# GTwoShield.net
KiCad netlist of a schematic drawn in EAGLE
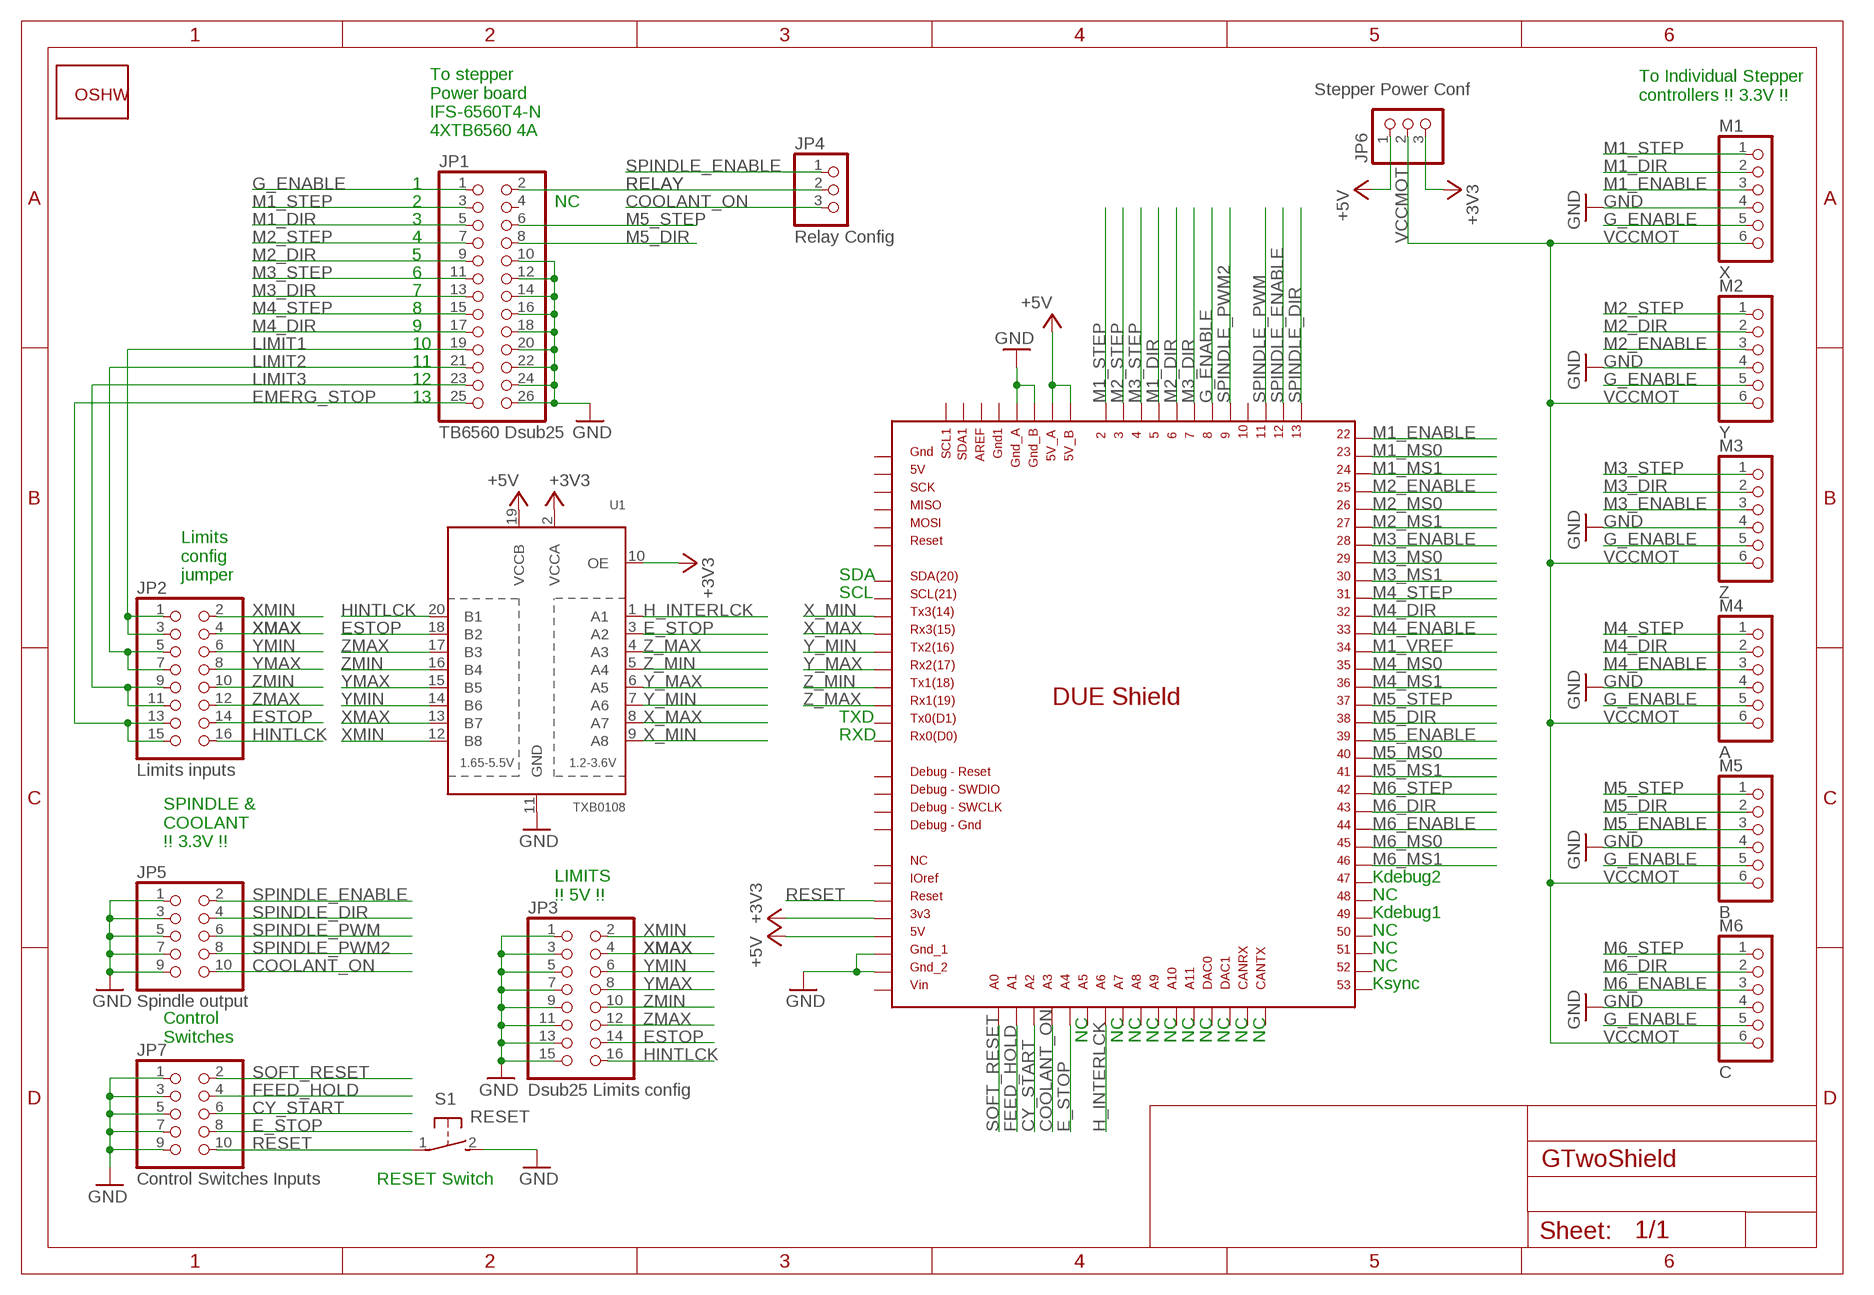
[diagram p0: schematic, sheet 1]

(export (version "E")
  (design (tool "Eeschema 10.0.6"))
  (components
    (comp (ref "GOLD_ORB_SM1")
      (value "OSHWLOGO_GOLD_ORB_MED")
      (footprint "eagle-import:OSHW1")
      (libsource (lib "eagle-import") (part "OSHWLOGO_GOLD_ORB_MED"))
    )
    (comp (ref "JP1")
      (value "TB6560 Dsub25")
      (footprint "eagle-import:2X13")
      (libsource (lib "eagle-import") (part "PINHD-2X13"))
    )
    (comp (ref "JP2")
      (value "Limits inputs")
      (footprint "eagle-import:2X08")
      (libsource (lib "eagle-import") (part "PINHD-2X8"))
    )
    (comp (ref "JP3")
      (value "Dsub25 Limits config")
      (footprint "eagle-import:2X08")
      (libsource (lib "eagle-import") (part "PINHD-2X8"))
    )
    (comp (ref "JP4")
      (value "Relay Config")
      (footprint "eagle-import:1X03")
      (libsource (lib "eagle-import") (part "PINHD-1X3"))
    )
    (comp (ref "JP5")
      (value "Spindle output")
      (footprint "eagle-import:2X05")
      (libsource (lib "eagle-import") (part "PINHD-2X5"))
    )
    (comp (ref "JP6")
      (value "Stepper Power Conf")
      (footprint "eagle-import:1X03")
      (libsource (lib "eagle-import") (part "PINHD-1X3"))
    )
    (comp (ref "JP7")
      (value "Control Switches Inputs")
      (footprint "eagle-import:2X05")
      (libsource (lib "eagle-import") (part "PINHD-2X5"))
    )
    (comp (ref "M1")
      (value "X")
      (footprint "eagle-import:1X06")
      (libsource (lib "eagle-import") (part "PINHD-1X6"))
    )
    (comp (ref "M2")
      (value "Y")
      (footprint "eagle-import:1X06")
      (libsource (lib "eagle-import") (part "PINHD-1X6"))
    )
    (comp (ref "M3")
      (value "Z")
      (footprint "eagle-import:1X06")
      (libsource (lib "eagle-import") (part "PINHD-1X6"))
    )
    (comp (ref "M4")
      (value "A")
      (footprint "eagle-import:1X06")
      (libsource (lib "eagle-import") (part "PINHD-1X6"))
    )
    (comp (ref "M5")
      (value "B")
      (footprint "eagle-import:1X06")
      (libsource (lib "eagle-import") (part "PINHD-1X6"))
    )
    (comp (ref "M6")
      (value "C")
      (footprint "eagle-import:1X06")
      (libsource (lib "eagle-import") (part "PINHD-1X6"))
    )
    (comp (ref "S1")
      (value "RESET")
      (footprint "eagle-import:B3F-31XX")
      (libsource (lib "eagle-import") (part "31-XX"))
    )
    (comp (ref "U$1")
      (value "DUE(NORMAL)")
      (footprint "eagle-import:DUE(NORMAL)")
      (libsource (lib "eagle-import") (part "DUE(NORMAL)"))
    )
    (comp (ref "U1")
      (value "TXB0108")
      (footprint "eagle-import:TSSOP20")
      (libsource (lib "eagle-import") (part "TXB0108PWR"))
    )
  )
  (nets
    (net (code "1") (name "+3V3") (class "Default")
      (node (ref "JP6") (pin "3") (pinfunction "3_3") (pintype "passive"))
      (node (ref "U$1") (pin "3V3") (pinfunction "3V3_3V3") (pintype "bidirectional"))
      (node (ref "U1") (pin "10") (pinfunction "OE_10") (pintype "bidirectional"))
      (node (ref "U1") (pin "2") (pinfunction "VCCA_2") (pintype "bidirectional"))
    )
    (net (code "2") (name "+5V") (class "Default")
      (node (ref "JP6") (pin "1") (pinfunction "1_1") (pintype "passive"))
      (node (ref "U$1") (pin "5V") (pinfunction "5V_5V") (pintype "bidirectional"))
      (node (ref "U$1") (pin "5V_A") (pinfunction "5V_A_5V_A") (pintype "bidirectional"))
      (node (ref "U$1") (pin "5V_B") (pinfunction "5V_B_5V_B") (pintype "bidirectional"))
      (node (ref "U1") (pin "19") (pinfunction "VCCB_19") (pintype "bidirectional"))
    )
    (net (code "3") (name "/COOLANT_ON") (class "Default")
      (node (ref "JP4") (pin "3") (pinfunction "3_3") (pintype "passive"))
      (node (ref "JP5") (pin "10") (pinfunction "10_10") (pintype "passive"))
      (node (ref "U$1") (pin "A3") (pinfunction "A3_A3") (pintype "bidirectional"))
    )
    (net (code "4") (name "/CY_START") (class "Default")
      (node (ref "JP7") (pin "6") (pinfunction "6_6") (pintype "passive"))
      (node (ref "U$1") (pin "A2") (pinfunction "A2_A2") (pintype "bidirectional"))
    )
    (net (code "5") (name "/EMERG_STOP") (class "Default")
      (node (ref "JP1") (pin "25") (pinfunction "25_25") (pintype "passive"))
      (node (ref "JP2") (pin "13") (pinfunction "13_13") (pintype "passive"))
      (node (ref "JP2") (pin "15") (pinfunction "15_15") (pintype "passive"))
    )
    (net (code "6") (name "/ESTOP") (class "Default")
      (node (ref "JP2") (pin "14") (pinfunction "14_14") (pintype "passive"))
      (node (ref "JP3") (pin "14") (pinfunction "14_14") (pintype "passive"))
      (node (ref "U1") (pin "18") (pinfunction "B2_18") (pintype "bidirectional"))
    )
    (net (code "7") (name "/E_STOP") (class "Default")
      (node (ref "JP7") (pin "8") (pinfunction "8_8") (pintype "passive"))
      (node (ref "U$1") (pin "A4") (pinfunction "A4_A4") (pintype "bidirectional"))
      (node (ref "U1") (pin "3") (pinfunction "A2_3") (pintype "bidirectional"))
    )
    (net (code "8") (name "/FEED_HOLD") (class "Default")
      (node (ref "JP7") (pin "4") (pinfunction "4_4") (pintype "passive"))
      (node (ref "U$1") (pin "A1") (pinfunction "A1_A1") (pintype "bidirectional"))
    )
    (net (code "9") (name "/G_ENABLE") (class "Default")
      (node (ref "JP1") (pin "1") (pinfunction "1_1") (pintype "passive"))
      (node (ref "M1") (pin "5") (pinfunction "5_5") (pintype "passive"))
      (node (ref "M2") (pin "5") (pinfunction "5_5") (pintype "passive"))
      (node (ref "M3") (pin "5") (pinfunction "5_5") (pintype "passive"))
      (node (ref "M4") (pin "5") (pinfunction "5_5") (pintype "passive"))
      (node (ref "M5") (pin "5") (pinfunction "5_5") (pintype "passive"))
      (node (ref "M6") (pin "5") (pinfunction "5_5") (pintype "passive"))
      (node (ref "U$1") (pin "8") (pinfunction "8_8") (pintype "bidirectional"))
    )
    (net (code "10") (name "/HINTLCK") (class "Default")
      (node (ref "JP2") (pin "16") (pinfunction "16_16") (pintype "passive"))
      (node (ref "JP3") (pin "16") (pinfunction "16_16") (pintype "passive"))
      (node (ref "U1") (pin "20") (pinfunction "B1_20") (pintype "bidirectional"))
    )
    (net (code "11") (name "/H_INTERLCK") (class "Default")
      (node (ref "U$1") (pin "A6") (pinfunction "A6_A6") (pintype "bidirectional"))
      (node (ref "U1") (pin "1") (pinfunction "A1_1") (pintype "bidirectional"))
    )
    (net (code "12") (name "/LIMIT1") (class "Default")
      (node (ref "JP1") (pin "19") (pinfunction "19_19") (pintype "passive"))
      (node (ref "JP2") (pin "1") (pinfunction "1_1") (pintype "passive"))
      (node (ref "JP2") (pin "3") (pinfunction "3_3") (pintype "passive"))
    )
    (net (code "13") (name "/LIMIT2") (class "Default")
      (node (ref "JP1") (pin "21") (pinfunction "21_21") (pintype "passive"))
      (node (ref "JP2") (pin "5") (pinfunction "5_5") (pintype "passive"))
      (node (ref "JP2") (pin "7") (pinfunction "7_7") (pintype "passive"))
    )
    (net (code "14") (name "/LIMIT3") (class "Default")
      (node (ref "JP1") (pin "23") (pinfunction "23_23") (pintype "passive"))
      (node (ref "JP2") (pin "11") (pinfunction "11_11") (pintype "passive"))
      (node (ref "JP2") (pin "9") (pinfunction "9_9") (pintype "passive"))
    )
    (net (code "15") (name "/M1_DIR") (class "Default")
      (node (ref "JP1") (pin "5") (pinfunction "5_5") (pintype "passive"))
      (node (ref "M1") (pin "2") (pinfunction "2_2") (pintype "passive"))
      (node (ref "U$1") (pin "5") (pinfunction "5_5") (pintype "bidirectional"))
    )
    (net (code "16") (name "/M1_ENABLE") (class "Default")
      (node (ref "M1") (pin "3") (pinfunction "3_3") (pintype "passive"))
      (node (ref "U$1") (pin "22") (pinfunction "22_22") (pintype "bidirectional"))
    )
    (net (code "17") (name "/M1_MS0") (class "Default")
      (node (ref "U$1") (pin "23") (pinfunction "23_23") (pintype "bidirectional"))
    )
    (net (code "18") (name "/M1_MS1") (class "Default")
      (node (ref "U$1") (pin "24") (pinfunction "24_24") (pintype "bidirectional"))
    )
    (net (code "19") (name "/M1_STEP") (class "Default")
      (node (ref "JP1") (pin "3") (pinfunction "3_3") (pintype "passive"))
      (node (ref "M1") (pin "1") (pinfunction "1_1") (pintype "passive"))
      (node (ref "U$1") (pin "2") (pinfunction "2_2") (pintype "bidirectional"))
    )
    (net (code "20") (name "/M1_VREF") (class "Default")
      (node (ref "U$1") (pin "34") (pinfunction "34_34") (pintype "bidirectional"))
    )
    (net (code "21") (name "/M2_DIR") (class "Default")
      (node (ref "JP1") (pin "9") (pinfunction "9_9") (pintype "passive"))
      (node (ref "M2") (pin "2") (pinfunction "2_2") (pintype "passive"))
      (node (ref "U$1") (pin "6") (pinfunction "6_6") (pintype "bidirectional"))
    )
    (net (code "22") (name "/M2_ENABLE") (class "Default")
      (node (ref "M2") (pin "3") (pinfunction "3_3") (pintype "passive"))
      (node (ref "U$1") (pin "25") (pinfunction "25_25") (pintype "bidirectional"))
    )
    (net (code "23") (name "/M2_MS0") (class "Default")
      (node (ref "U$1") (pin "26") (pinfunction "26_26") (pintype "bidirectional"))
    )
    (net (code "24") (name "/M2_MS1") (class "Default")
      (node (ref "U$1") (pin "27") (pinfunction "27_27") (pintype "bidirectional"))
    )
    (net (code "25") (name "/M2_STEP") (class "Default")
      (node (ref "JP1") (pin "7") (pinfunction "7_7") (pintype "passive"))
      (node (ref "M2") (pin "1") (pinfunction "1_1") (pintype "passive"))
      (node (ref "U$1") (pin "3") (pinfunction "3_3") (pintype "bidirectional"))
    )
    (net (code "26") (name "/M3_DIR") (class "Default")
      (node (ref "JP1") (pin "13") (pinfunction "13_13") (pintype "passive"))
      (node (ref "M3") (pin "2") (pinfunction "2_2") (pintype "passive"))
      (node (ref "U$1") (pin "7") (pinfunction "7_7") (pintype "bidirectional"))
    )
    (net (code "27") (name "/M3_ENABLE") (class "Default")
      (node (ref "M3") (pin "3") (pinfunction "3_3") (pintype "passive"))
      (node (ref "U$1") (pin "28") (pinfunction "28_28") (pintype "bidirectional"))
    )
    (net (code "28") (name "/M3_MS0") (class "Default")
      (node (ref "U$1") (pin "29") (pinfunction "29_29") (pintype "bidirectional"))
    )
    (net (code "29") (name "/M3_MS1") (class "Default")
      (node (ref "U$1") (pin "30") (pinfunction "30_30") (pintype "bidirectional"))
    )
    (net (code "30") (name "/M3_STEP") (class "Default")
      (node (ref "JP1") (pin "11") (pinfunction "11_11") (pintype "passive"))
      (node (ref "M3") (pin "1") (pinfunction "1_1") (pintype "passive"))
      (node (ref "U$1") (pin "4") (pinfunction "4_4") (pintype "bidirectional"))
    )
    (net (code "31") (name "/M4_DIR") (class "Default")
      (node (ref "JP1") (pin "17") (pinfunction "17_17") (pintype "passive"))
      (node (ref "M4") (pin "2") (pinfunction "2_2") (pintype "passive"))
      (node (ref "U$1") (pin "32") (pinfunction "32_32") (pintype "bidirectional"))
    )
    (net (code "32") (name "/M4_ENABLE") (class "Default")
      (node (ref "M4") (pin "3") (pinfunction "3_3") (pintype "passive"))
      (node (ref "U$1") (pin "33") (pinfunction "33_33") (pintype "bidirectional"))
    )
    (net (code "33") (name "/M4_MS0") (class "Default")
      (node (ref "U$1") (pin "35") (pinfunction "35_35") (pintype "bidirectional"))
    )
    (net (code "34") (name "/M4_MS1") (class "Default")
      (node (ref "U$1") (pin "36") (pinfunction "36_36") (pintype "bidirectional"))
    )
    (net (code "35") (name "/M4_STEP") (class "Default")
      (node (ref "JP1") (pin "15") (pinfunction "15_15") (pintype "passive"))
      (node (ref "M4") (pin "1") (pinfunction "1_1") (pintype "passive"))
      (node (ref "U$1") (pin "31") (pinfunction "31_31") (pintype "bidirectional"))
    )
    (net (code "36") (name "/M5_DIR") (class "Default")
      (node (ref "JP1") (pin "8") (pinfunction "8_8") (pintype "passive"))
      (node (ref "M5") (pin "2") (pinfunction "2_2") (pintype "passive"))
      (node (ref "U$1") (pin "38") (pinfunction "38_38") (pintype "bidirectional"))
    )
    (net (code "37") (name "/M5_ENABLE") (class "Default")
      (node (ref "M5") (pin "3") (pinfunction "3_3") (pintype "passive"))
      (node (ref "U$1") (pin "39") (pinfunction "39_39") (pintype "bidirectional"))
    )
    (net (code "38") (name "/M5_MS0") (class "Default")
      (node (ref "U$1") (pin "40") (pinfunction "40_40") (pintype "bidirectional"))
    )
    (net (code "39") (name "/M5_MS1") (class "Default")
      (node (ref "U$1") (pin "41") (pinfunction "41_41") (pintype "bidirectional"))
    )
    (net (code "40") (name "/M5_STEP") (class "Default")
      (node (ref "JP1") (pin "6") (pinfunction "6_6") (pintype "passive"))
      (node (ref "M5") (pin "1") (pinfunction "1_1") (pintype "passive"))
      (node (ref "U$1") (pin "37") (pinfunction "37_37") (pintype "bidirectional"))
    )
    (net (code "41") (name "/M6_DIR") (class "Default")
      (node (ref "M6") (pin "2") (pinfunction "2_2") (pintype "passive"))
      (node (ref "U$1") (pin "43") (pinfunction "43_43") (pintype "bidirectional"))
    )
    (net (code "42") (name "/M6_ENABLE") (class "Default")
      (node (ref "M6") (pin "3") (pinfunction "3_3") (pintype "passive"))
      (node (ref "U$1") (pin "44") (pinfunction "44_44") (pintype "bidirectional"))
    )
    (net (code "43") (name "/M6_MS0") (class "Default")
      (node (ref "U$1") (pin "45") (pinfunction "45_45") (pintype "bidirectional"))
    )
    (net (code "44") (name "/M6_MS1") (class "Default")
      (node (ref "U$1") (pin "46") (pinfunction "46_46") (pintype "bidirectional"))
    )
    (net (code "45") (name "/M6_STEP") (class "Default")
      (node (ref "M6") (pin "1") (pinfunction "1_1") (pintype "passive"))
      (node (ref "U$1") (pin "42") (pinfunction "42_42") (pintype "bidirectional"))
    )
    (net (code "46") (name "/RELAY") (class "Default")
      (node (ref "JP1") (pin "2") (pinfunction "2_2") (pintype "passive"))
      (node (ref "JP4") (pin "2") (pinfunction "2_2") (pintype "passive"))
    )
    (net (code "47") (name "/RESET") (class "Default")
      (node (ref "JP7") (pin "10") (pinfunction "10_10") (pintype "passive"))
      (node (ref "S1") (pin "1") (pinfunction "P_1") (pintype "passive"))
      (node (ref "U$1") (pin "RESET") (pinfunction "RESET_RESET") (pintype "bidirectional"))
    )
    (net (code "48") (name "/SOFT_RESET") (class "Default")
      (node (ref "JP7") (pin "2") (pinfunction "2_2") (pintype "passive"))
      (node (ref "U$1") (pin "A0") (pinfunction "A0_A0") (pintype "bidirectional"))
    )
    (net (code "49") (name "/SPINDLE_DIR") (class "Default")
      (node (ref "JP5") (pin "4") (pinfunction "4_4") (pintype "passive"))
      (node (ref "U$1") (pin "13") (pinfunction "13_13") (pintype "bidirectional"))
    )
    (net (code "50") (name "/SPINDLE_ENABLE") (class "Default")
      (node (ref "JP4") (pin "1") (pinfunction "1_1") (pintype "passive"))
      (node (ref "JP5") (pin "2") (pinfunction "2_2") (pintype "passive"))
      (node (ref "U$1") (pin "12") (pinfunction "12_12") (pintype "bidirectional"))
    )
    (net (code "51") (name "/SPINDLE_PWM") (class "Default")
      (node (ref "JP5") (pin "6") (pinfunction "6_6") (pintype "passive"))
      (node (ref "U$1") (pin "11") (pinfunction "11_11") (pintype "bidirectional"))
    )
    (net (code "52") (name "/SPINDLE_PWM2") (class "Default")
      (node (ref "JP5") (pin "8") (pinfunction "8_8") (pintype "passive"))
      (node (ref "U$1") (pin "9") (pinfunction "9_9") (pintype "bidirectional"))
    )
    (net (code "53") (name "/VCCMOT") (class "Default")
      (node (ref "JP6") (pin "2") (pinfunction "2_2") (pintype "passive"))
      (node (ref "M1") (pin "6") (pinfunction "6_6") (pintype "passive"))
      (node (ref "M2") (pin "6") (pinfunction "6_6") (pintype "passive"))
      (node (ref "M3") (pin "6") (pinfunction "6_6") (pintype "passive"))
      (node (ref "M4") (pin "6") (pinfunction "6_6") (pintype "passive"))
      (node (ref "M5") (pin "6") (pinfunction "6_6") (pintype "passive"))
      (node (ref "M6") (pin "6") (pinfunction "6_6") (pintype "passive"))
    )
    (net (code "54") (name "/XMAX") (class "Default")
      (node (ref "JP2") (pin "4") (pinfunction "4_4") (pintype "passive"))
      (node (ref "JP3") (pin "4") (pinfunction "4_4") (pintype "passive"))
      (node (ref "U1") (pin "13") (pinfunction "B7_13") (pintype "bidirectional"))
    )
    (net (code "55") (name "/XMIN") (class "Default")
      (node (ref "JP2") (pin "2") (pinfunction "2_2") (pintype "passive"))
      (node (ref "JP3") (pin "2") (pinfunction "2_2") (pintype "passive"))
      (node (ref "U1") (pin "12") (pinfunction "B8_12") (pintype "bidirectional"))
    )
    (net (code "56") (name "/X_MAX") (class "Default")
      (node (ref "U$1") (pin "RX3") (pinfunction "RX3_RX3") (pintype "bidirectional"))
      (node (ref "U1") (pin "8") (pinfunction "A7_8") (pintype "bidirectional"))
    )
    (net (code "57") (name "/X_MIN") (class "Default")
      (node (ref "U$1") (pin "TX3") (pinfunction "TX3_TX3") (pintype "bidirectional"))
      (node (ref "U1") (pin "9") (pinfunction "A8_9") (pintype "bidirectional"))
    )
    (net (code "58") (name "/YMAX") (class "Default")
      (node (ref "JP2") (pin "8") (pinfunction "8_8") (pintype "passive"))
      (node (ref "JP3") (pin "8") (pinfunction "8_8") (pintype "passive"))
      (node (ref "U1") (pin "15") (pinfunction "B5_15") (pintype "bidirectional"))
    )
    (net (code "59") (name "/YMIN") (class "Default")
      (node (ref "JP2") (pin "6") (pinfunction "6_6") (pintype "passive"))
      (node (ref "JP3") (pin "6") (pinfunction "6_6") (pintype "passive"))
      (node (ref "U1") (pin "14") (pinfunction "B6_14") (pintype "bidirectional"))
    )
    (net (code "60") (name "/Y_MAX") (class "Default")
      (node (ref "U$1") (pin "RX2") (pinfunction "RX2_RX2") (pintype "bidirectional"))
      (node (ref "U1") (pin "6") (pinfunction "A5_6") (pintype "bidirectional"))
    )
    (net (code "61") (name "/Y_MIN") (class "Default")
      (node (ref "U$1") (pin "TX2") (pinfunction "TX2_TX2") (pintype "bidirectional"))
      (node (ref "U1") (pin "7") (pinfunction "A6_7") (pintype "bidirectional"))
    )
    (net (code "62") (name "/ZMAX") (class "Default")
      (node (ref "JP2") (pin "12") (pinfunction "12_12") (pintype "passive"))
      (node (ref "JP3") (pin "12") (pinfunction "12_12") (pintype "passive"))
      (node (ref "U1") (pin "17") (pinfunction "B3_17") (pintype "bidirectional"))
    )
    (net (code "63") (name "/ZMIN") (class "Default")
      (node (ref "JP2") (pin "10") (pinfunction "10_10") (pintype "passive"))
      (node (ref "JP3") (pin "10") (pinfunction "10_10") (pintype "passive"))
      (node (ref "U1") (pin "16") (pinfunction "B4_16") (pintype "bidirectional"))
    )
    (net (code "64") (name "/Z_MAX") (class "Default")
      (node (ref "U$1") (pin "RX1") (pinfunction "RX1_RX1") (pintype "bidirectional"))
      (node (ref "U1") (pin "4") (pinfunction "A3_4") (pintype "bidirectional"))
    )
    (net (code "65") (name "/Z_MIN") (class "Default")
      (node (ref "U$1") (pin "TX1") (pinfunction "TX1_TX1") (pintype "bidirectional"))
      (node (ref "U1") (pin "5") (pinfunction "A4_5") (pintype "bidirectional"))
    )
    (net (code "66") (name "GND") (class "Default")
      (node (ref "JP1") (pin "10") (pinfunction "10_10") (pintype "passive"))
      (node (ref "JP1") (pin "12") (pinfunction "12_12") (pintype "passive"))
      (node (ref "JP1") (pin "14") (pinfunction "14_14") (pintype "passive"))
      (node (ref "JP1") (pin "16") (pinfunction "16_16") (pintype "passive"))
      (node (ref "JP1") (pin "18") (pinfunction "18_18") (pintype "passive"))
      (node (ref "JP1") (pin "20") (pinfunction "20_20") (pintype "passive"))
      (node (ref "JP1") (pin "22") (pinfunction "22_22") (pintype "passive"))
      (node (ref "JP1") (pin "24") (pinfunction "24_24") (pintype "passive"))
      (node (ref "JP1") (pin "26") (pinfunction "26_26") (pintype "passive"))
      (node (ref "JP3") (pin "1") (pinfunction "1_1") (pintype "passive"))
      (node (ref "JP3") (pin "11") (pinfunction "11_11") (pintype "passive"))
      (node (ref "JP3") (pin "13") (pinfunction "13_13") (pintype "passive"))
      (node (ref "JP3") (pin "15") (pinfunction "15_15") (pintype "passive"))
      (node (ref "JP3") (pin "3") (pinfunction "3_3") (pintype "passive"))
      (node (ref "JP3") (pin "5") (pinfunction "5_5") (pintype "passive"))
      (node (ref "JP3") (pin "7") (pinfunction "7_7") (pintype "passive"))
      (node (ref "JP3") (pin "9") (pinfunction "9_9") (pintype "passive"))
      (node (ref "JP5") (pin "1") (pinfunction "1_1") (pintype "passive"))
      (node (ref "JP5") (pin "3") (pinfunction "3_3") (pintype "passive"))
      (node (ref "JP5") (pin "5") (pinfunction "5_5") (pintype "passive"))
      (node (ref "JP5") (pin "7") (pinfunction "7_7") (pintype "passive"))
      (node (ref "JP5") (pin "9") (pinfunction "9_9") (pintype "passive"))
      (node (ref "JP7") (pin "1") (pinfunction "1_1") (pintype "passive"))
      (node (ref "JP7") (pin "3") (pinfunction "3_3") (pintype "passive"))
      (node (ref "JP7") (pin "5") (pinfunction "5_5") (pintype "passive"))
      (node (ref "JP7") (pin "7") (pinfunction "7_7") (pintype "passive"))
      (node (ref "JP7") (pin "9") (pinfunction "9_9") (pintype "passive"))
      (node (ref "M1") (pin "4") (pinfunction "4_4") (pintype "passive"))
      (node (ref "M2") (pin "4") (pinfunction "4_4") (pintype "passive"))
      (node (ref "M3") (pin "4") (pinfunction "4_4") (pintype "passive"))
      (node (ref "M4") (pin "4") (pinfunction "4_4") (pintype "passive"))
      (node (ref "M5") (pin "4") (pinfunction "4_4") (pintype "passive"))
      (node (ref "M6") (pin "4") (pinfunction "4_4") (pintype "passive"))
      (node (ref "S1") (pin "2") (pinfunction "S_2") (pintype "passive"))
      (node (ref "U$1") (pin "GND_1") (pinfunction "GND_1_GND_1") (pintype "bidirectional"))
      (node (ref "U$1") (pin "GND_2") (pinfunction "GND_2_GND_2") (pintype "bidirectional"))
      (node (ref "U$1") (pin "GND_A") (pinfunction "GND_A_GND_A") (pintype "bidirectional"))
      (node (ref "U$1") (pin "GND_B") (pinfunction "GND_B_GND_B") (pintype "bidirectional"))
      (node (ref "U1") (pin "11") (pinfunction "GND_11") (pintype "bidirectional"))
    )
    (net (code "67") (name "unconnected-(JP1-Pad4)") (class "Default")
      (node (ref "JP1") (pin "4") (pinfunction "4_4") (pintype "passive"))
    )
    (net (code "68") (name "unconnected-(U$1-Pad5V_ICSP)") (class "Default")
      (node (ref "U$1") (pin "5V_ICSP") (pinfunction "5V_ICSP_5V_ICSP") (pintype "bidirectional"))
    )
    (net (code "69") (name "unconnected-(U$1-Pad10)") (class "Default")
      (node (ref "U$1") (pin "10") (pinfunction "10_10") (pintype "bidirectional"))
    )
    (net (code "70") (name "unconnected-(U$1-Pad47)") (class "Default")
      (node (ref "U$1") (pin "47") (pinfunction "47_47") (pintype "bidirectional"))
    )
    (net (code "71") (name "unconnected-(U$1-Pad48)") (class "Default")
      (node (ref "U$1") (pin "48") (pinfunction "48_48") (pintype "bidirectional"))
    )
    (net (code "72") (name "unconnected-(U$1-Pad49)") (class "Default")
      (node (ref "U$1") (pin "49") (pinfunction "49_49") (pintype "bidirectional"))
    )
    (net (code "73") (name "unconnected-(U$1-Pad50)") (class "Default")
      (node (ref "U$1") (pin "50") (pinfunction "50_50") (pintype "bidirectional"))
    )
    (net (code "74") (name "unconnected-(U$1-Pad51)") (class "Default")
      (node (ref "U$1") (pin "51") (pinfunction "51_51") (pintype "bidirectional"))
    )
    (net (code "75") (name "unconnected-(U$1-Pad52)") (class "Default")
      (node (ref "U$1") (pin "52") (pinfunction "52_52") (pintype "bidirectional"))
    )
    (net (code "76") (name "unconnected-(U$1-Pad53)") (class "Default")
      (node (ref "U$1") (pin "53") (pinfunction "53_53") (pintype "bidirectional"))
    )
    (net (code "77") (name "unconnected-(U$1-PadA5)") (class "Default")
      (node (ref "U$1") (pin "A5") (pinfunction "A5_A5") (pintype "bidirectional"))
    )
    (net (code "78") (name "unconnected-(U$1-PadA7)") (class "Default")
      (node (ref "U$1") (pin "A7") (pinfunction "A7_A7") (pintype "bidirectional"))
    )
    (net (code "79") (name "unconnected-(U$1-PadA8)") (class "Default")
      (node (ref "U$1") (pin "A8") (pinfunction "A8_A8") (pintype "bidirectional"))
    )
    (net (code "80") (name "unconnected-(U$1-PadA9)") (class "Default")
      (node (ref "U$1") (pin "A9") (pinfunction "A9_A9") (pintype "bidirectional"))
    )
    (net (code "81") (name "unconnected-(U$1-PadA10)") (class "Default")
      (node (ref "U$1") (pin "A10") (pinfunction "A10_A10") (pintype "bidirectional"))
    )
    (net (code "82") (name "unconnected-(U$1-PadA11)") (class "Default")
      (node (ref "U$1") (pin "A11") (pinfunction "A11_A11") (pintype "bidirectional"))
    )
    (net (code "83") (name "unconnected-(U$1-PadAREF)") (class "Default")
      (node (ref "U$1") (pin "AREF") (pinfunction "AREF_AREF") (pintype "bidirectional"))
    )
    (net (code "84") (name "unconnected-(U$1-PadCANRX)") (class "Default")
      (node (ref "U$1") (pin "CANRX") (pinfunction "CANRX_CANRX") (pintype "bidirectional"))
    )
    (net (code "85") (name "unconnected-(U$1-PadCANTX)") (class "Default")
      (node (ref "U$1") (pin "CANTX") (pinfunction "CANTX_CANTX") (pintype "bidirectional"))
    )
    (net (code "86") (name "unconnected-(U$1-PadDAC0)") (class "Default")
      (node (ref "U$1") (pin "DAC0") (pinfunction "DAC0_DAC0") (pintype "bidirectional"))
    )
    (net (code "87") (name "unconnected-(U$1-PadDAC1)") (class "Default")
      (node (ref "U$1") (pin "DAC1") (pinfunction "DAC1_DAC1") (pintype "bidirectional"))
    )
    (net (code "88") (name "unconnected-(U$1-PadGND1)") (class "Default")
      (node (ref "U$1") (pin "GND1") (pinfunction "GND1_GND1") (pintype "bidirectional"))
    )
    (net (code "89") (name "unconnected-(U$1-PadGND_DEBUG)") (class "Default")
      (node (ref "U$1") (pin "GND_DEBUG") (pinfunction "GND_DEBUG_GND_DEBUG") (pintype "bidirectional"))
    )
    (net (code "90") (name "unconnected-(U$1-PadGND_ICSP)") (class "Default")
      (node (ref "U$1") (pin "GND_ICSP") (pinfunction "GND_ICSP_GND_ICSP") (pintype "bidirectional"))
    )
    (net (code "91") (name "unconnected-(U$1-PadIOREF)") (class "Default")
      (node (ref "U$1") (pin "IOREF") (pinfunction "IOREF_IOREF") (pintype "bidirectional"))
    )
    (net (code "92") (name "unconnected-(U$1-PadMISO_ICSP)") (class "Default")
      (node (ref "U$1") (pin "MISO_ICSP") (pinfunction "MISO_ICSP_MISO_ICSP") (pintype "bidirectional"))
    )
    (net (code "93") (name "unconnected-(U$1-PadMOSI_ICSP)") (class "Default")
      (node (ref "U$1") (pin "MOSI_ICSP") (pinfunction "MOSI_ICSP_MOSI_ICSP") (pintype "bidirectional"))
    )
    (net (code "94") (name "unconnected-(U$1-PadNC)") (class "Default")
      (node (ref "U$1") (pin "NC") (pinfunction "NC_NC") (pintype "bidirectional"))
    )
    (net (code "95") (name "unconnected-(U$1-PadRESET_DEBUG)") (class "Default")
      (node (ref "U$1") (pin "RESET_DEBUG") (pinfunction "RESET_DEBUG_RESET_DEBUG") (pintype "bidirectional"))
    )
    (net (code "96") (name "unconnected-(U$1-PadRESET_ICSP)") (class "Default")
      (node (ref "U$1") (pin "RESET_ICSP") (pinfunction "RESET_ICSP_RESET_ICSP") (pintype "bidirectional"))
    )
    (net (code "97") (name "unconnected-(U$1-PadRX0)") (class "Default")
      (node (ref "U$1") (pin "RX0") (pinfunction "RX0_RX0") (pintype "bidirectional"))
    )
    (net (code "98") (name "unconnected-(U$1-PadSCK_ICSP)") (class "Default")
      (node (ref "U$1") (pin "SCK_ICSP") (pinfunction "SCK_ICSP_SCK_ICSP") (pintype "bidirectional"))
    )
    (net (code "99") (name "unconnected-(U$1-PadSCL)") (class "Default")
      (node (ref "U$1") (pin "SCL") (pinfunction "SCL_SCL") (pintype "bidirectional"))
    )
    (net (code "100") (name "unconnected-(U$1-PadSCL1)") (class "Default")
      (node (ref "U$1") (pin "SCL1") (pinfunction "SCL1_SCL1") (pintype "bidirectional"))
    )
    (net (code "101") (name "unconnected-(U$1-PadSDA)") (class "Default")
      (node (ref "U$1") (pin "SDA") (pinfunction "SDA_SDA") (pintype "bidirectional"))
    )
    (net (code "102") (name "unconnected-(U$1-PadSDA1)") (class "Default")
      (node (ref "U$1") (pin "SDA1") (pinfunction "SDA1_SDA1") (pintype "bidirectional"))
    )
    (net (code "103") (name "unconnected-(U$1-PadSWCLK_DEBUG)") (class "Default")
      (node (ref "U$1") (pin "SWCLK_DEBUG") (pinfunction "SWCLK_DEBUG_SWCLK_DEBUG") (pintype "bidirectional"))
    )
    (net (code "104") (name "unconnected-(U$1-PadSWDIO_DEBUG)") (class "Default")
      (node (ref "U$1") (pin "SWDIO_DEBUG") (pinfunction "SWDIO_DEBUG_SWDIO_DEBUG") (pintype "bidirectional"))
    )
    (net (code "105") (name "unconnected-(U$1-PadTX0)") (class "Default")
      (node (ref "U$1") (pin "TX0") (pinfunction "TX0_TX0") (pintype "bidirectional"))
    )
    (net (code "106") (name "unconnected-(U$1-PadVIN)") (class "Default")
      (node (ref "U$1") (pin "VIN") (pinfunction "VIN_VIN") (pintype "bidirectional"))
    )
  )
)
